# main.net
KiCad netlist of a schematic drawn in Altium Designer
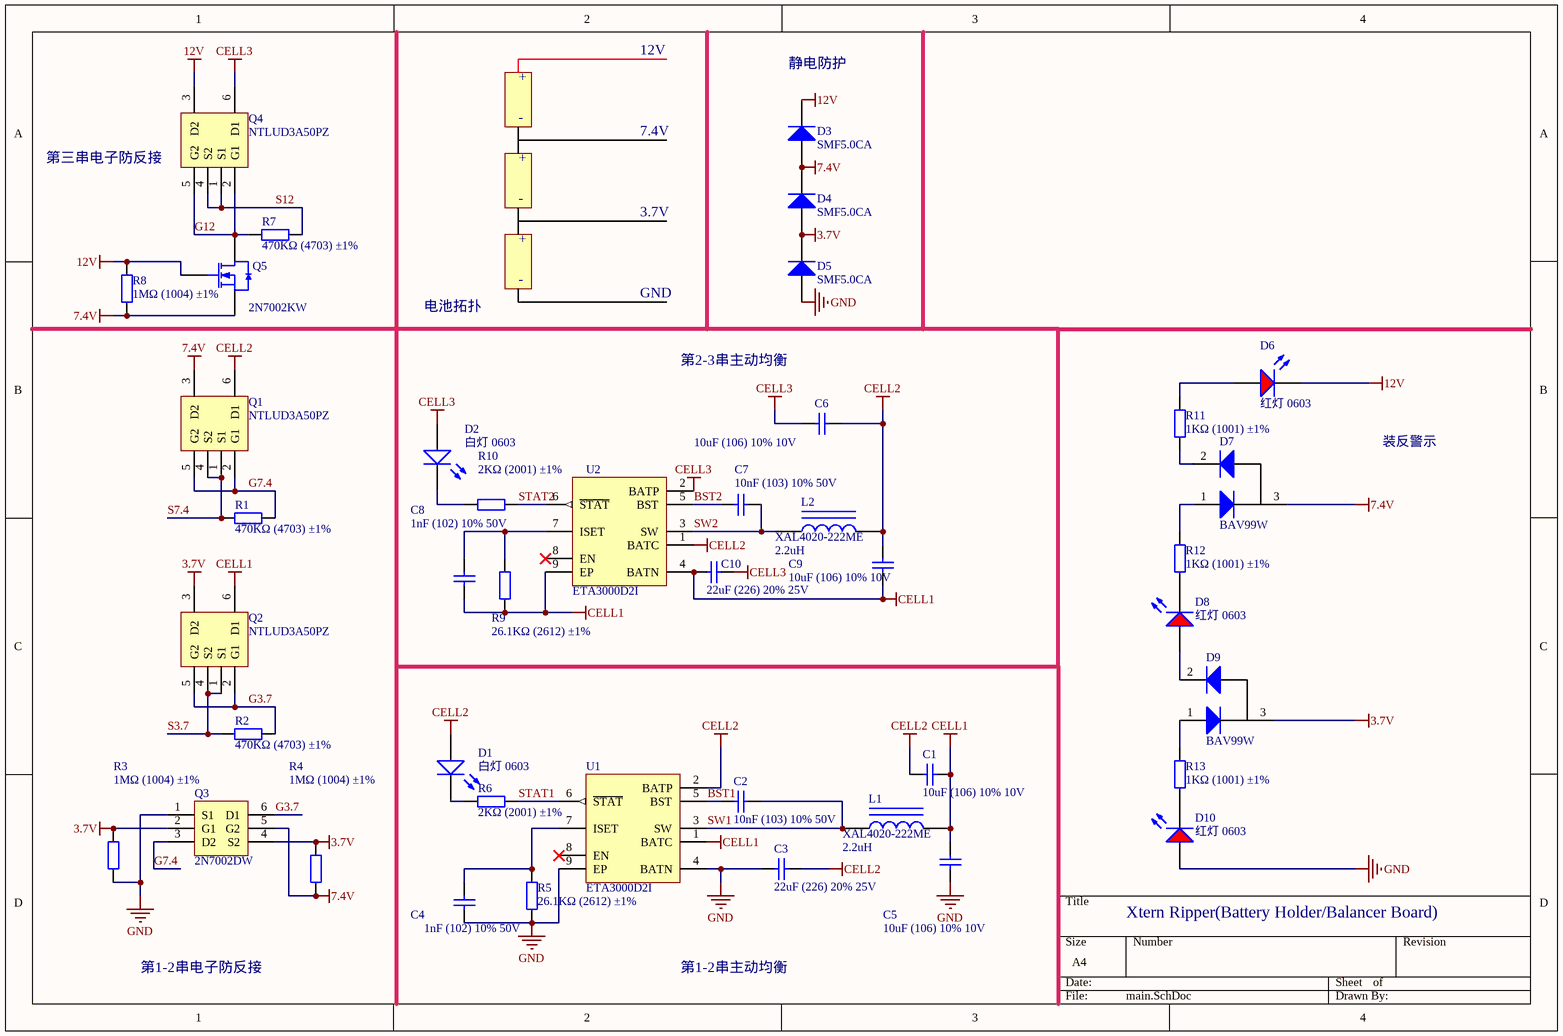
[diagram p0: main.SchDoc]

(export (version "E")
  (design (tool "Eeschema 10.0.6"))
  (components
    (comp (ref "C1")
      (value "10uF (106) 10% 10V")
      (footprint "0603_C")
      (description "贴片电容")
      (libsource (lib "Miscellaneous Devices LC") (part "0603 10uF (106) 10% 10V"))
    )
    (comp (ref "C2")
      (value "10nF (103) 10% 50V")
      (footprint "0402_C")
      (description "贴片电容")
      (libsource (lib "Miscellaneous Devices LC") (part "0402 10nF (103) 10% 50V"))
    )
    (comp (ref "C3")
      (value "22uF (226) 20% 25V")
      (footprint "0805_C")
      (description "贴片电容")
      (libsource (lib "Miscellaneous Devices LC") (part "0805 22uF (226) 20% 25V"))
    )
    (comp (ref "C4")
      (value "1nF (102) 10% 50V")
      (footprint "0402_C")
      (description "贴片电容")
      (libsource (lib "Miscellaneous Devices LC") (part "0402 1nF (102) 10% 50V"))
    )
    (comp (ref "C5")
      (value "10uF (106) 10% 10V")
      (footprint "0603_C")
      (description "贴片电容")
      (libsource (lib "Miscellaneous Devices LC") (part "0603 10uF (106) 10% 10V"))
    )
    (comp (ref "C6")
      (value "10uF (106) 10% 10V")
      (footprint "0603_C")
      (description "贴片电容")
      (libsource (lib "Miscellaneous Devices LC") (part "0603 10uF (106) 10% 10V"))
    )
    (comp (ref "C7")
      (value "10nF (103) 10% 50V")
      (footprint "0402_C")
      (description "贴片电容")
      (libsource (lib "Miscellaneous Devices LC") (part "0402 10nF (103) 10% 50V"))
    )
    (comp (ref "C8")
      (value "1nF (102) 10% 50V")
      (footprint "0402_C")
      (description "贴片电容")
      (libsource (lib "Miscellaneous Devices LC") (part "0402 1nF (102) 10% 50V"))
    )
    (comp (ref "C9")
      (value "10uF (106) 10% 10V")
      (footprint "0603_C")
      (description "贴片电容")
      (libsource (lib "Miscellaneous Devices LC") (part "0603 10uF (106) 10% 10V"))
    )
    (comp (ref "C10")
      (value "22uF (226) 20% 25V")
      (footprint "0805_C")
      (description "贴片电容")
      (libsource (lib "Miscellaneous Devices LC") (part "0805 22uF (226) 20% 25V"))
    )
    (comp (ref "D1")
      (value "白灯 0603")
      (footprint "0603_LED_S1")
      (description "发光二极管")
      (libsource (lib "Miscellaneous Devices LC") (part "0603 白灯"))
    )
    (comp (ref "D2")
      (value "白灯 0603")
      (footprint "0603_LED_S1")
      (description "发光二极管")
      (libsource (lib "Miscellaneous Devices LC") (part "0603 白灯"))
    )
    (comp (ref "D3")
      (value "SMF5.0CA")
      (footprint "SOD-123")
      (description "TVS二极管")
      (libsource (lib "Miscellaneous Devices LC") (part "SOD-123 B5819W  SL"))
    )
    (comp (ref "D4")
      (value "SMF5.0CA")
      (footprint "SOD-123")
      (description "TVS二极管")
      (libsource (lib "Miscellaneous Devices LC") (part "SOD-123 B5819W  SL"))
    )
    (comp (ref "D5")
      (value "SMF5.0CA")
      (footprint "SOD-123")
      (description "TVS二极管")
      (libsource (lib "Miscellaneous Devices LC") (part "SOD-123 B5819W  SL"))
    )
    (comp (ref "D6")
      (value "红灯 0603")
      (footprint "0603_LED_S1")
      (description "发光二极管")
      (libsource (lib "Miscellaneous Devices LC") (part "0603 红灯"))
    )
    (comp (ref "D7")
      (value "BAV99W")
      (footprint "SC70-3")
      (description "开关二极管")
      (libsource (lib "Miscellaneous Devices LC") (part "SOT-23 BAV99 A7W"))
    )
    (comp (ref "D8")
      (value "红灯 0603")
      (footprint "0603_LED_S1")
      (description "发光二极管")
      (libsource (lib "Miscellaneous Devices LC") (part "0603 红灯"))
    )
    (comp (ref "D9")
      (value "BAV99W")
      (footprint "SC70-3")
      (description "开关二极管")
      (libsource (lib "Miscellaneous Devices LC") (part "SOT-23 BAV99 A7W"))
    )
    (comp (ref "D10")
      (value "红灯 0603")
      (footprint "0603_LED_S1")
      (description "发光二极管")
      (libsource (lib "Miscellaneous Devices LC") (part "0603 红灯"))
    )
    (comp (ref "L1")
      (value "XAL4020-222ME")
      (footprint "XAL4020-xxxME")
      (description "Coilcraft XAL4020 Series")
      (fields (field (name "ALTIUM_VALUE") "2.2uH") (field (name "PUBLISHER") "Altium Limited"))
      (libsource (lib "Miscellaneous Devices") (part "Inductor Iron"))
    )
    (comp (ref "L2")
      (value "XAL4020-222ME")
      (footprint "XAL4020-xxxME")
      (description "Coilcraft XAL4020 Series")
      (fields (field (name "ALTIUM_VALUE") "2.2uH") (field (name "PUBLISHER") "Altium Limited"))
      (libsource (lib "Miscellaneous Devices") (part "Inductor Iron"))
    )
    (comp (ref "Q1")
      (value "NTLUD3A50PZ")
      (footprint "UDFN-6_L2.0-W2.0-P0.65-BL_NTLUD3A50PZ")
      (description "Dual Symmetric P-MOS -20V -5.6A")
      (libsource (lib "custom") (part "NTLUD3A50PZ"))
    )
    (comp (ref "Q2")
      (value "NTLUD3A50PZ")
      (footprint "UDFN-6_L2.0-W2.0-P0.65-BL_NTLUD3A50PZ")
      (description "Dual Symmetric P-MOS -20V -5.6A")
      (libsource (lib "custom") (part "NTLUD3A50PZ"))
    )
    (comp (ref "Q3")
      (value "2N7002DW")
      (footprint "SC70-6")
      (description "Dual N-Channel MOSFET 60V340mA SOT-363")
      (libsource (lib "custom") (part "2N7002DW"))
    )
    (comp (ref "Q4")
      (value "NTLUD3A50PZ")
      (footprint "UDFN-6_L2.0-W2.0-P0.65-BL_NTLUD3A50PZ")
      (description "Dual Symmetric P-MOS -20V -5.6A")
      (libsource (lib "custom") (part "NTLUD3A50PZ"))
    )
    (comp (ref "Q5")
      (value "2N7002KW")
      (footprint "SC70-3")
      (description "MOS(场效应管)")
      (libsource (lib "Miscellaneous Devices LC") (part "2N7002 7002"))
    )
    (comp (ref "R1")
      (value "470KΩ (4703) ±1%")
      (footprint "0402_R")
      (description "贴片电阻")
      (libsource (lib "Miscellaneous Devices LC") (part "0402 68KΩ (6802) 1%"))
    )
    (comp (ref "R2")
      (value "470KΩ (4703) ±1%")
      (footprint "0402_R")
      (description "贴片电阻")
      (libsource (lib "Miscellaneous Devices LC") (part "0402 68KΩ (6802) 1%"))
    )
    (comp (ref "R3")
      (value "1MΩ (1004) ±1%")
      (footprint "0402_R")
      (description "贴片电阻")
      (libsource (lib "Miscellaneous Devices LC") (part "0402 1MΩ (1004) 1%"))
    )
    (comp (ref "R4")
      (value "1MΩ (1004) ±1%")
      (footprint "0402_R")
      (description "贴片电阻")
      (libsource (lib "Miscellaneous Devices LC") (part "0402 1MΩ (1004) 1%"))
    )
    (comp (ref "R5")
      (value "26.1KΩ (2612) ±1%")
      (footprint "0402_R")
      (description "贴片电阻")
      (libsource (lib "Miscellaneous Devices LC") (part "0402 20KΩ (2002) 1%"))
    )
    (comp (ref "R6")
      (value "2KΩ (2001) ±1%")
      (footprint "0402_R")
      (description "贴片电阻")
      (libsource (lib "Miscellaneous Devices LC") (part "0402 3.3KΩ (3301) 1%"))
    )
    (comp (ref "R7")
      (value "470KΩ (4703) ±1%")
      (footprint "0402_R")
      (description "贴片电阻")
      (libsource (lib "Miscellaneous Devices LC") (part "0402 68KΩ (6802) 1%"))
    )
    (comp (ref "R8")
      (value "1MΩ (1004) ±1%")
      (footprint "0402_R")
      (description "贴片电阻")
      (libsource (lib "Miscellaneous Devices LC") (part "0402 1MΩ (1004) 1%"))
    )
    (comp (ref "R9")
      (value "26.1KΩ (2612) ±1%")
      (footprint "0402_R")
      (description "贴片电阻")
      (libsource (lib "Miscellaneous Devices LC") (part "0402 20KΩ (2002) 1%"))
    )
    (comp (ref "R10")
      (value "2KΩ (2001) ±1%")
      (footprint "0402_R")
      (description "贴片电阻")
      (libsource (lib "Miscellaneous Devices LC") (part "0402 3.3KΩ (3301) 1%"))
    )
    (comp (ref "R11")
      (value "1KΩ (1001) ±1%")
      (footprint "0402_R")
      (description "贴片电阻")
      (libsource (lib "Miscellaneous Devices LC") (part "0402 1KΩ (1001) 1%"))
    )
    (comp (ref "R12")
      (value "1KΩ (1001) ±1%")
      (footprint "0402_R")
      (description "贴片电阻")
      (libsource (lib "Miscellaneous Devices LC") (part "0402 1KΩ (1001) 1%"))
    )
    (comp (ref "R13")
      (value "1KΩ (1001) ±1%")
      (footprint "0402_R")
      (description "贴片电阻")
      (libsource (lib "Miscellaneous Devices LC") (part "0402 1KΩ (1001) 1%"))
    )
    (comp (ref "U1")
      (value "ETA3000D2I")
      (footprint "DFN2x2-8L")
      (description "2串锂电池电感主动均衡芯片,DFN2*2封装 2A均衡电流")
      (libsource (lib "custom") (part "ETA3000D2I"))
    )
    (comp (ref "U2")
      (value "ETA3000D2I")
      (footprint "DFN2x2-8L")
      (description "2串锂电池电感主动均衡芯片,DFN2*2封装 2A均衡电流")
      (libsource (lib "custom") (part "ETA3000D2I"))
    )
  )
  (nets
    (net (code "1") (name "/BST1") (class "Default")
      (node (ref "C2") (pin "2") (pinfunction "2_2") (pintype "passive"))
      (node (ref "U1") (pin "5") (pinfunction "BST_5") (pintype "power_in"))
    )
    (net (code "2") (name "/BST2") (class "Default")
      (node (ref "C7") (pin "1") (pinfunction "1_1") (pintype "passive"))
      (node (ref "U2") (pin "5") (pinfunction "BST_5") (pintype "power_in"))
    )
    (net (code "3") (name "/G3.7") (class "Default")
      (node (ref "Q2") (pin "2") (pinfunction "G1_2") (pintype "passive"))
      (node (ref "Q2") (pin "5") (pinfunction "G2_5") (pintype "passive"))
      (node (ref "Q3") (pin "6") (pinfunction "D1_6") (pintype "passive"))
      (node (ref "R2") (pin "2") (pinfunction "2_2") (pintype "passive"))
    )
    (net (code "4") (name "/G7.4") (class "Default")
      (node (ref "Q1") (pin "2") (pinfunction "G1_2") (pintype "passive"))
      (node (ref "Q1") (pin "5") (pinfunction "G2_5") (pintype "passive"))
      (node (ref "Q3") (pin "3") (pinfunction "D2_3") (pintype "passive"))
      (node (ref "R1") (pin "2") (pinfunction "2_2") (pintype "passive"))
    )
    (net (code "5") (name "/G12") (class "Default")
      (node (ref "Q4") (pin "2") (pinfunction "G1_2") (pintype "passive"))
      (node (ref "Q4") (pin "5") (pinfunction "G2_5") (pintype "passive"))
      (node (ref "Q5") (pin "3") (pinfunction "D_3") (pintype "passive"))
      (node (ref "R7") (pin "1") (pinfunction "1_1") (pintype "passive"))
    )
    (net (code "6") (name "/S3.7") (class "Default")
      (node (ref "Q2") (pin "1") (pinfunction "S1_1") (pintype "passive"))
      (node (ref "Q2") (pin "4") (pinfunction "S2_4") (pintype "passive"))
      (node (ref "R2") (pin "1") (pinfunction "1_1") (pintype "passive"))
    )
    (net (code "7") (name "/S7.4") (class "Default")
      (node (ref "Q1") (pin "1") (pinfunction "S1_1") (pintype "passive"))
      (node (ref "Q1") (pin "4") (pinfunction "S2_4") (pintype "passive"))
      (node (ref "R1") (pin "1") (pinfunction "1_1") (pintype "passive"))
    )
    (net (code "8") (name "/S12") (class "Default")
      (node (ref "Q4") (pin "1") (pinfunction "S1_1") (pintype "passive"))
      (node (ref "Q4") (pin "4") (pinfunction "S2_4") (pintype "passive"))
      (node (ref "R7") (pin "2") (pinfunction "2_2") (pintype "passive"))
    )
    (net (code "9") (name "/STAT1") (class "Default")
      (node (ref "R6") (pin "2") (pinfunction "2_2") (pintype "passive"))
      (node (ref "U1") (pin "6") (pinfunction "~{STAT}_6") (pintype "output"))
    )
    (net (code "10") (name "/STAT2") (class "Default")
      (node (ref "R10") (pin "2") (pinfunction "2_2") (pintype "passive"))
      (node (ref "U2") (pin "6") (pinfunction "~{STAT}_6") (pintype "output"))
    )
    (net (code "11") (name "/SW1") (class "Default")
      (node (ref "C2") (pin "1") (pinfunction "1_1") (pintype "passive"))
      (node (ref "L1") (pin "1") (pinfunction "1_1") (pintype "passive"))
      (node (ref "U1") (pin "3") (pinfunction "SW_3") (pintype "power_in"))
    )
    (net (code "12") (name "/SW2") (class "Default")
      (node (ref "C7") (pin "2") (pinfunction "2_2") (pintype "passive"))
      (node (ref "L2") (pin "1") (pinfunction "1_1") (pintype "passive"))
      (node (ref "U2") (pin "3") (pinfunction "SW_3") (pintype "power_in"))
    )
    (net (code "13") (name "3.7V") (class "Default")
      (node (ref "D4") (pin "1") (pinfunction "A_1") (pintype "passive"))
      (node (ref "D5") (pin "2") (pinfunction "K_2") (pintype "passive"))
      (node (ref "D9") (pin "3") (pinfunction "K_3") (pintype "passive"))
      (node (ref "Q2") (pin "3") (pinfunction "D2_3") (pintype "passive"))
      (node (ref "Q3") (pin "2") (pinfunction "G1_2") (pintype "passive"))
      (node (ref "Q3") (pin "4") (pinfunction "S2_4") (pintype "passive"))
      (node (ref "R3") (pin "2") (pinfunction "2_2") (pintype "passive"))
      (node (ref "R4") (pin "2") (pinfunction "2_2") (pintype "passive"))
    )
    (net (code "14") (name "7.4V") (class "Default")
      (node (ref "D3") (pin "1") (pinfunction "A_1") (pintype "passive"))
      (node (ref "D4") (pin "2") (pinfunction "K_2") (pintype "passive"))
      (node (ref "D7") (pin "3") (pinfunction "K_3") (pintype "passive"))
      (node (ref "Q1") (pin "3") (pinfunction "D2_3") (pintype "passive"))
      (node (ref "Q3") (pin "5") (pinfunction "G2_5") (pintype "passive"))
      (node (ref "Q5") (pin "2") (pinfunction "S_2") (pintype "passive"))
      (node (ref "R4") (pin "1") (pinfunction "1_1") (pintype "passive"))
      (node (ref "R8") (pin "1") (pinfunction "1_1") (pintype "passive"))
    )
    (net (code "15") (name "12V") (class "Default")
      (node (ref "D3") (pin "2") (pinfunction "K_2") (pintype "passive"))
      (node (ref "D6") (pin "K") (pinfunction "K_K") (pintype "passive"))
      (node (ref "Q4") (pin "3") (pinfunction "D2_3") (pintype "passive"))
      (node (ref "Q5") (pin "1") (pinfunction "G_1") (pintype "passive"))
      (node (ref "R8") (pin "2") (pinfunction "2_2") (pintype "passive"))
    )
    (net (code "16") (name "CELL1") (class "Default")
      (node (ref "C1") (pin "2") (pinfunction "2_2") (pintype "passive"))
      (node (ref "C10") (pin "1") (pinfunction "1_1") (pintype "passive"))
      (node (ref "C5") (pin "2") (pinfunction "2_2") (pintype "passive"))
      (node (ref "C8") (pin "1") (pinfunction "1_1") (pintype "passive"))
      (node (ref "C9") (pin "1") (pinfunction "1_1") (pintype "passive"))
      (node (ref "L1") (pin "2") (pinfunction "2_2") (pintype "passive"))
      (node (ref "Q2") (pin "6") (pinfunction "D1_6") (pintype "passive"))
      (node (ref "R9") (pin "1") (pinfunction "1_1") (pintype "passive"))
      (node (ref "U1") (pin "1") (pinfunction "BATC_1") (pintype "power_in"))
      (node (ref "U2") (pin "4") (pinfunction "BATN_4") (pintype "power_in"))
      (node (ref "U2") (pin "9") (pinfunction "EP_9") (pintype "passive"))
    )
    (net (code "17") (name "CELL2") (class "Default")
      (node (ref "C1") (pin "1") (pinfunction "1_1") (pintype "passive"))
      (node (ref "C3") (pin "2") (pinfunction "2_2") (pintype "passive"))
      (node (ref "C6") (pin "2") (pinfunction "2_2") (pintype "passive"))
      (node (ref "C9") (pin "2") (pinfunction "2_2") (pintype "passive"))
      (node (ref "D1") (pin "A") (pinfunction "A_A") (pintype "passive"))
      (node (ref "L2") (pin "2") (pinfunction "2_2") (pintype "passive"))
      (node (ref "Q1") (pin "6") (pinfunction "D1_6") (pintype "passive"))
      (node (ref "U1") (pin "2") (pinfunction "BATP_2") (pintype "power_in"))
      (node (ref "U2") (pin "1") (pinfunction "BATC_1") (pintype "power_in"))
    )
    (net (code "18") (name "CELL3") (class "Default")
      (node (ref "C10") (pin "2") (pinfunction "2_2") (pintype "passive"))
      (node (ref "C6") (pin "1") (pinfunction "1_1") (pintype "passive"))
      (node (ref "D2") (pin "A") (pinfunction "A_A") (pintype "passive"))
      (node (ref "Q4") (pin "6") (pinfunction "D1_6") (pintype "passive"))
      (node (ref "U2") (pin "2") (pinfunction "BATP_2") (pintype "power_in"))
    )
    (net (code "19") (name "GND") (class "Default")
      (node (ref "C3") (pin "1") (pinfunction "1_1") (pintype "passive"))
      (node (ref "C4") (pin "1") (pinfunction "1_1") (pintype "passive"))
      (node (ref "C5") (pin "1") (pinfunction "1_1") (pintype "passive"))
      (node (ref "D10") (pin "A") (pinfunction "A_A") (pintype "passive"))
      (node (ref "D5") (pin "1") (pinfunction "A_1") (pintype "passive"))
      (node (ref "Q3") (pin "1") (pinfunction "S1_1") (pintype "passive"))
      (node (ref "R3") (pin "1") (pinfunction "1_1") (pintype "passive"))
      (node (ref "R5") (pin "1") (pinfunction "1_1") (pintype "passive"))
      (node (ref "U1") (pin "4") (pinfunction "BATN_4") (pintype "power_in"))
      (node (ref "U1") (pin "9") (pinfunction "EP_9") (pintype "passive"))
    )
    (net (code "20") (name "Net-(D1-PadK)") (class "Default")
      (node (ref "D1") (pin "K") (pinfunction "K_K") (pintype "passive"))
      (node (ref "R6") (pin "1") (pinfunction "1_1") (pintype "passive"))
    )
    (net (code "21") (name "Net-(D2-PadK)") (class "Default")
      (node (ref "D2") (pin "K") (pinfunction "K_K") (pintype "passive"))
      (node (ref "R10") (pin "1") (pinfunction "1_1") (pintype "passive"))
    )
    (net (code "22") (name "Net-(D6-PadA)") (class "Default")
      (node (ref "D6") (pin "A") (pinfunction "A_A") (pintype "passive"))
      (node (ref "R11") (pin "2") (pinfunction "2_2") (pintype "passive"))
    )
    (net (code "23") (name "Net-(D7-A-Pad1)") (class "Default")
      (node (ref "D7") (pin "1") (pinfunction "A_1") (pintype "passive"))
      (node (ref "R12") (pin "2") (pinfunction "2_2") (pintype "passive"))
    )
    (net (code "24") (name "Net-(D7-A-Pad2)") (class "Default")
      (node (ref "D7") (pin "2") (pinfunction "A_2") (pintype "passive"))
      (node (ref "R11") (pin "1") (pinfunction "1_1") (pintype "passive"))
    )
    (net (code "25") (name "Net-(D8-PadA)") (class "Default")
      (node (ref "D8") (pin "A") (pinfunction "A_A") (pintype "passive"))
      (node (ref "D9") (pin "2") (pinfunction "A_2") (pintype "passive"))
    )
    (net (code "26") (name "Net-(D8-PadK)") (class "Default")
      (node (ref "D8") (pin "K") (pinfunction "K_K") (pintype "passive"))
      (node (ref "R12") (pin "1") (pinfunction "1_1") (pintype "passive"))
    )
    (net (code "27") (name "Net-(D9-A-Pad1)") (class "Default")
      (node (ref "D9") (pin "1") (pinfunction "A_1") (pintype "passive"))
      (node (ref "R13") (pin "2") (pinfunction "2_2") (pintype "passive"))
    )
    (net (code "28") (name "Net-(D10-PadK)") (class "Default")
      (node (ref "D10") (pin "K") (pinfunction "K_K") (pintype "passive"))
      (node (ref "R13") (pin "1") (pinfunction "1_1") (pintype "passive"))
    )
    (net (code "29") (name "Net-(U1-ISET)") (class "Default")
      (node (ref "C4") (pin "2") (pinfunction "2_2") (pintype "passive"))
      (node (ref "R5") (pin "2") (pinfunction "2_2") (pintype "passive"))
      (node (ref "U1") (pin "7") (pinfunction "ISET_7") (pintype "passive"))
    )
    (net (code "30") (name "Net-(U2-ISET)") (class "Default")
      (node (ref "C8") (pin "2") (pinfunction "2_2") (pintype "passive"))
      (node (ref "R9") (pin "2") (pinfunction "2_2") (pintype "passive"))
      (node (ref "U2") (pin "7") (pinfunction "ISET_7") (pintype "passive"))
    )
    (net (code "31") (name "unconnected-(U1-EN-Pad8)") (class "Default")
      (node (ref "U1") (pin "8") (pinfunction "EN_8") (pintype "passive+no_connect"))
    )
    (net (code "32") (name "unconnected-(U2-EN-Pad8)") (class "Default")
      (node (ref "U2") (pin "8") (pinfunction "EN_8") (pintype "passive+no_connect"))
    )
  )
)
